# WS2812B.net
KiCad netlist of a schematic drawn in Altium Designer
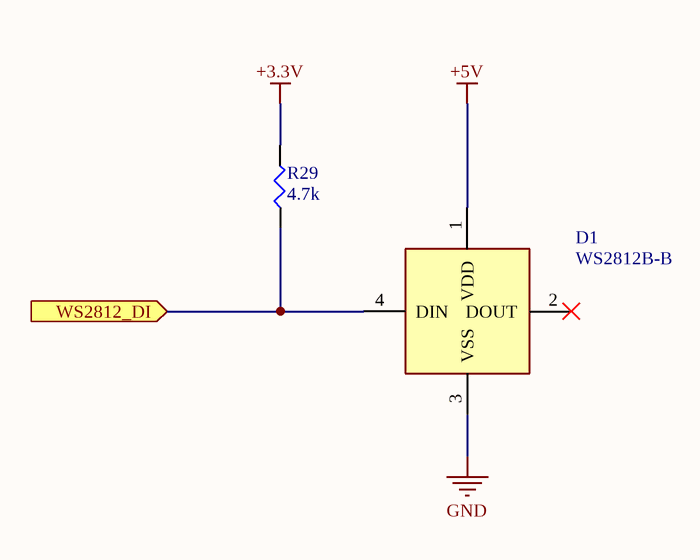
[diagram p0: WS2812B.SchDoc]

(export (version "E")
  (design (tool "Eeschema 10.0.6"))
  (components
    (comp (ref "D1")
      (value "WS2812B-B")
      (footprint "SamacSys:WS2812BB")
      (description "LED")
      (libsource (lib "SomoPowerPackControl") (part "WS2812B-B"))
    )
    (comp (ref "R29")
      (value "4.7k")
      (footprint "SMD-0402-RES")
      (description "RES SMD 4.7K OHM 1% 1/10W 0402")
      (fields
        (field (name "PART NUMBER") "ERJ-2RKF4701X")
        (field (name "DIGI-KEY PART NUMBER") "P4.70KLCT-ND")
      )
      (libsource (lib "Panasonic_ERJ_0402") (part "ERJ-2RKF4701X"))
    )
  )
  (nets
    (net (code "1") (name "+3.3V") (class "Default")
      (node (ref "R29") (pin "2") (pinfunction "2_2") (pintype "passive"))
    )
    (net (code "2") (name "+5V") (class "Default")
      (node (ref "D1") (pin "1") (pinfunction "VDD_1") (pintype "passive"))
    )
    (net (code "3") (name "/WS2812_DI") (class "Default")
      (node (ref "D1") (pin "4") (pinfunction "DIN_4") (pintype "passive"))
      (node (ref "R29") (pin "1") (pinfunction "1_1") (pintype "passive"))
    )
    (net (code "4") (name "GND") (class "Default")
      (node (ref "D1") (pin "3") (pinfunction "VSS_3") (pintype "passive"))
    )
    (net (code "5") (name "unconnected-(D1-DOUT-Pad2)") (class "Default")
      (node (ref "D1") (pin "2") (pinfunction "DOUT_2") (pintype "passive+no_connect"))
    )
  )
)
